# rad_detector_v500_PSU.net
KiCad netlist of a schematic drawn in Altium Designer
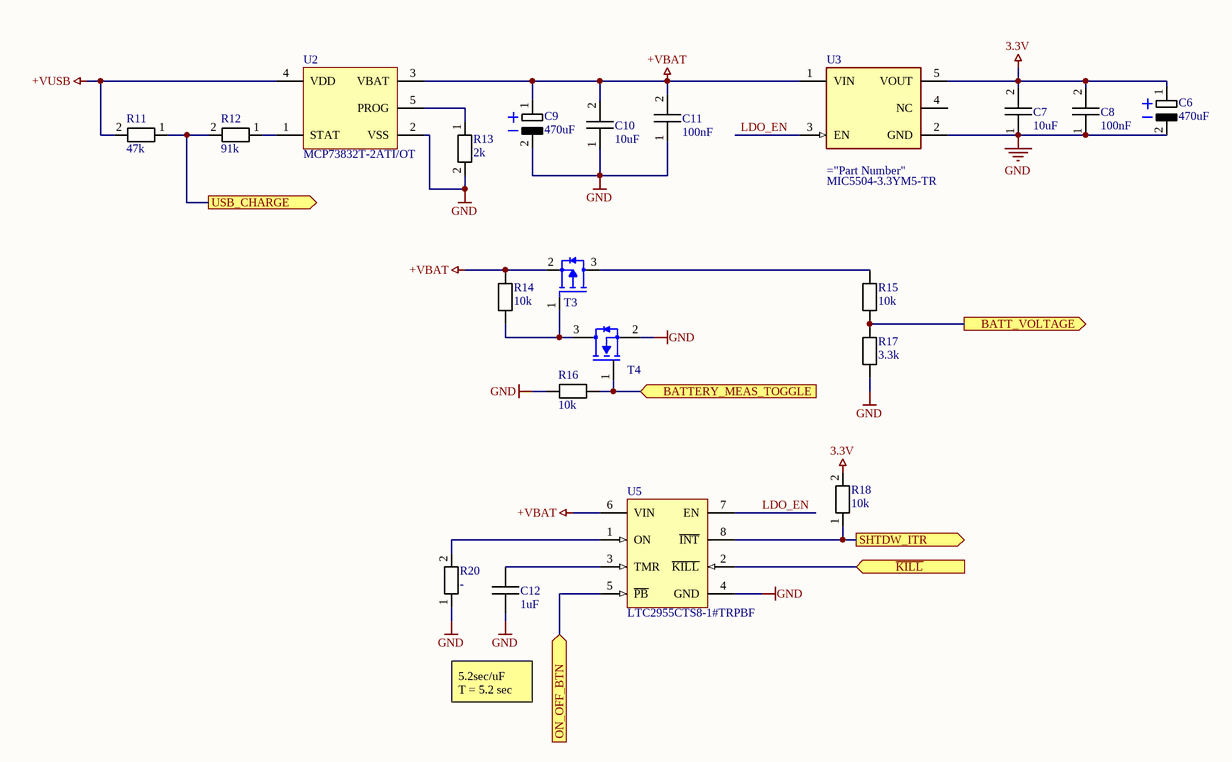
[diagram p0: rad_detector_v500_PSU.SchDoc]

(export (version "E")
  (design (tool "Eeschema 10.0.6"))
  (components
    (comp (ref "C6")
      (value "470uF")
      (footprint "CAPAE9383X110M")
      (libsource (lib "Schlib1") (part "CAPACITOR_ELCO"))
    )
    (comp (ref "C7") (value "10uF") (footprint "1210_C") (libsource (lib "Schlib1") (part "CAPACITOR")))
    (comp (ref "C8") (value "100nF") (footprint "0805_C") (libsource (lib "Schlib1") (part "CAPACITOR")))
    (comp (ref "C9")
      (value "470uF")
      (footprint "CAPAE9383X110M")
      (libsource (lib "Schlib1") (part "CAPACITOR_ELCO"))
    )
    (comp (ref "C10") (value "10uF") (footprint "1210_C") (libsource (lib "Schlib1") (part "CAPACITOR")))
    (comp (ref "C11") (value "100nF") (footprint "0805_C") (libsource (lib "Schlib1") (part "CAPACITOR")))
    (comp (ref "C12") (value "1uF") (footprint "0805_C") (libsource (lib "") (part "CAPACITOR_1")))
    (comp (ref "R11") (value "47k") (footprint "0805") (libsource (lib "") (part "RESISTOR_1")))
    (comp (ref "R12") (value "91k") (footprint "0805") (libsource (lib "") (part "RESISTOR_1")))
    (comp (ref "R13") (value "2k") (footprint "0805") (libsource (lib "") (part "RESISTOR_1")))
    (comp (ref "R14") (value "10k") (footprint "0805") (libsource (lib "Schlib1") (part "RESISTOR")))
    (comp (ref "R15") (value "10k") (footprint "0805") (libsource (lib "Schlib1") (part "RESISTOR")))
    (comp (ref "R16") (value "10k") (footprint "0805") (libsource (lib "Schlib1") (part "RESISTOR")))
    (comp (ref "R17") (value "3.3k") (footprint "0805") (libsource (lib "Schlib1") (part "RESISTOR")))
    (comp (ref "R18") (value "10k") (footprint "0805") (libsource (lib "") (part "RESISTOR_1")))
    (comp (ref "R20") (value "-") (footprint "0805") (libsource (lib "") (part "RESISTOR_1")))
    (comp (ref "T3")
      (value "BSS84")
      (footprint "SOT23")
      (description "P-Chanel MOSFET")
      (libsource (lib "Schlib1") (part "BSS84"))
    )
    (comp (ref "T4")
      (value "MMBF170")
      (footprint "SOT23")
      (description "N MOSFET")
      (libsource (lib "Schlib1") (part "MMBF170"))
    )
    (comp (ref "U2")
      (value "MCP73832T-2ATI/OT")
      (footprint "SOT23-5")
      (libsource (lib "pwr_mgt") (part "MCP73832T-2ATI/OT"))
    )
    (comp (ref "U3")
      (value "MIC5504-3.3YM5-TR")
      (footprint "SOT23-5")
      (libsource (lib "pwr_mgt") (part "MIC5504-3.3YM5-TR"))
    )
    (comp (ref "U5")
      (value "LTC2955CTS8-1#TRPBF")
      (footprint "LT-TS8-8-TSOT-23_V")
      (libsource (lib "ic_modules") (part "LTC2955CTS8-1"))
    )
  )
  (nets
    (net (code "1") (name "+VBAT") (class "Default")
      (node (ref "C10") (pin "2") (pinfunction "2_2") (pintype "passive"))
      (node (ref "C11") (pin "2") (pinfunction "2_2") (pintype "passive"))
      (node (ref "C9") (pin "1") (pinfunction "1_1") (pintype "passive"))
      (node (ref "R14") (pin "2") (pinfunction "1_2") (pintype "passive"))
      (node (ref "T3") (pin "2") (pinfunction "S_2") (pintype "passive"))
      (node (ref "U2") (pin "3") (pinfunction "VBAT_3") (pintype "power_in"))
      (node (ref "U3") (pin "1") (pinfunction "VIN_1") (pintype "power_in"))
      (node (ref "U5") (pin "6") (pinfunction "VIN_6") (pintype "power_in"))
    )
    (net (code "2") (name "+VUSB") (class "Default")
      (node (ref "R11") (pin "2") (pinfunction "1_2") (pintype "passive"))
      (node (ref "U2") (pin "4") (pinfunction "VDD_4") (pintype "power_in"))
    )
    (net (code "3") (name "/BATTERY_MEAS_TOGGLE") (class "Default")
      (node (ref "R16") (pin "2") (pinfunction "1_2") (pintype "passive"))
      (node (ref "T4") (pin "1") (pinfunction "Gate_1") (pintype "passive"))
    )
    (net (code "4") (name "/BATT_VOLTAGE") (class "Default")
      (node (ref "R15") (pin "1") (pinfunction "0_1") (pintype "passive"))
      (node (ref "R17") (pin "2") (pinfunction "1_2") (pintype "passive"))
    )
    (net (code "5") (name "/LDO_EN") (class "Default")
      (node (ref "U3") (pin "3") (pinfunction "EN_3") (pintype "input"))
      (node (ref "U5") (pin "7") (pinfunction "EN_7") (pintype "open_collector"))
    )
    (net (code "6") (name "/ON_OFF_BTN") (class "Default")
      (node (ref "U5") (pin "5") (pinfunction "~{PB}_5") (pintype "input"))
    )
    (net (code "7") (name "/SHTDW_ITR") (class "Default")
      (node (ref "R18") (pin "1") (pinfunction "0_1") (pintype "passive"))
      (node (ref "U5") (pin "8") (pinfunction "~{INT}_8") (pintype "open_collector"))
    )
    (net (code "8") (name "/USB_CHARGE") (class "Default")
      (node (ref "R11") (pin "1") (pinfunction "0_1") (pintype "passive"))
      (node (ref "R12") (pin "2") (pinfunction "1_2") (pintype "passive"))
    )
    (net (code "9") (name "/~{KILL}") (class "Default")
      (node (ref "U5") (pin "2") (pinfunction "~{KILL}_2") (pintype "input"))
    )
    (net (code "10") (name "3.3V") (class "Default")
      (node (ref "C6") (pin "1") (pinfunction "1_1") (pintype "passive"))
      (node (ref "C7") (pin "2") (pinfunction "2_2") (pintype "passive"))
      (node (ref "C8") (pin "2") (pinfunction "2_2") (pintype "passive"))
      (node (ref "R18") (pin "2") (pinfunction "1_2") (pintype "passive"))
      (node (ref "U3") (pin "5") (pinfunction "VOUT_5") (pintype "power_in"))
    )
    (net (code "11") (name "GND") (class "Default")
      (node (ref "C10") (pin "1") (pinfunction "1_1") (pintype "passive"))
      (node (ref "C11") (pin "1") (pinfunction "1_1") (pintype "passive"))
      (node (ref "C12") (pin "2") (pinfunction "2_2") (pintype "passive"))
      (node (ref "C6") (pin "2") (pinfunction "2_2") (pintype "passive"))
      (node (ref "C7") (pin "1") (pinfunction "1_1") (pintype "passive"))
      (node (ref "C8") (pin "1") (pinfunction "1_1") (pintype "passive"))
      (node (ref "C9") (pin "2") (pinfunction "2_2") (pintype "passive"))
      (node (ref "R13") (pin "2") (pinfunction "1_2") (pintype "passive"))
      (node (ref "R16") (pin "1") (pinfunction "0_1") (pintype "passive"))
      (node (ref "R17") (pin "1") (pinfunction "0_1") (pintype "passive"))
      (node (ref "R20") (pin "1") (pinfunction "0_1") (pintype "passive"))
      (node (ref "T4") (pin "2") (pinfunction "Source_2") (pintype "passive"))
      (node (ref "U2") (pin "2") (pinfunction "VSS_2") (pintype "power_in"))
      (node (ref "U3") (pin "2") (pinfunction "GND_2") (pintype "power_in"))
      (node (ref "U5") (pin "4") (pinfunction "GND_4") (pintype "power_in"))
    )
    (net (code "12") (name "Net-(R12-0)") (class "Default")
      (node (ref "R12") (pin "1") (pinfunction "0_1") (pintype "passive"))
      (node (ref "U2") (pin "1") (pinfunction "STAT_1") (pintype "open_collector"))
    )
    (net (code "13") (name "Net-(R13-0)") (class "Default")
      (node (ref "R13") (pin "1") (pinfunction "0_1") (pintype "passive"))
      (node (ref "U2") (pin "5") (pinfunction "PROG_5") (pintype "passive"))
    )
    (net (code "14") (name "Net-(R14-0)") (class "Default")
      (node (ref "R14") (pin "1") (pinfunction "0_1") (pintype "passive"))
      (node (ref "T3") (pin "1") (pinfunction "G_1") (pintype "passive"))
      (node (ref "T4") (pin "3") (pinfunction "Drain_3") (pintype "passive"))
    )
    (net (code "15") (name "Net-(R15-1)") (class "Default")
      (node (ref "R15") (pin "2") (pinfunction "1_2") (pintype "passive"))
      (node (ref "T3") (pin "3") (pinfunction "D_3") (pintype "passive"))
    )
    (net (code "16") (name "Net-(R20-1)") (class "Default")
      (node (ref "R20") (pin "2") (pinfunction "1_2") (pintype "passive"))
      (node (ref "U5") (pin "1") (pinfunction "ON_1") (pintype "input"))
    )
    (net (code "17") (name "Net-(U5-TMR)") (class "Default")
      (node (ref "C12") (pin "1") (pinfunction "1_1") (pintype "passive"))
      (node (ref "U5") (pin "3") (pinfunction "TMR_3") (pintype "input"))
    )
    (net (code "18") (name "unconnected-(U3-NC-Pad4)") (class "Default")
      (node (ref "U3") (pin "4") (pinfunction "NC_4") (pintype "passive"))
    )
  )
)
